# VariablePWMDriverSchematic.net
KiCad netlist of a schematic drawn in Altium Designer
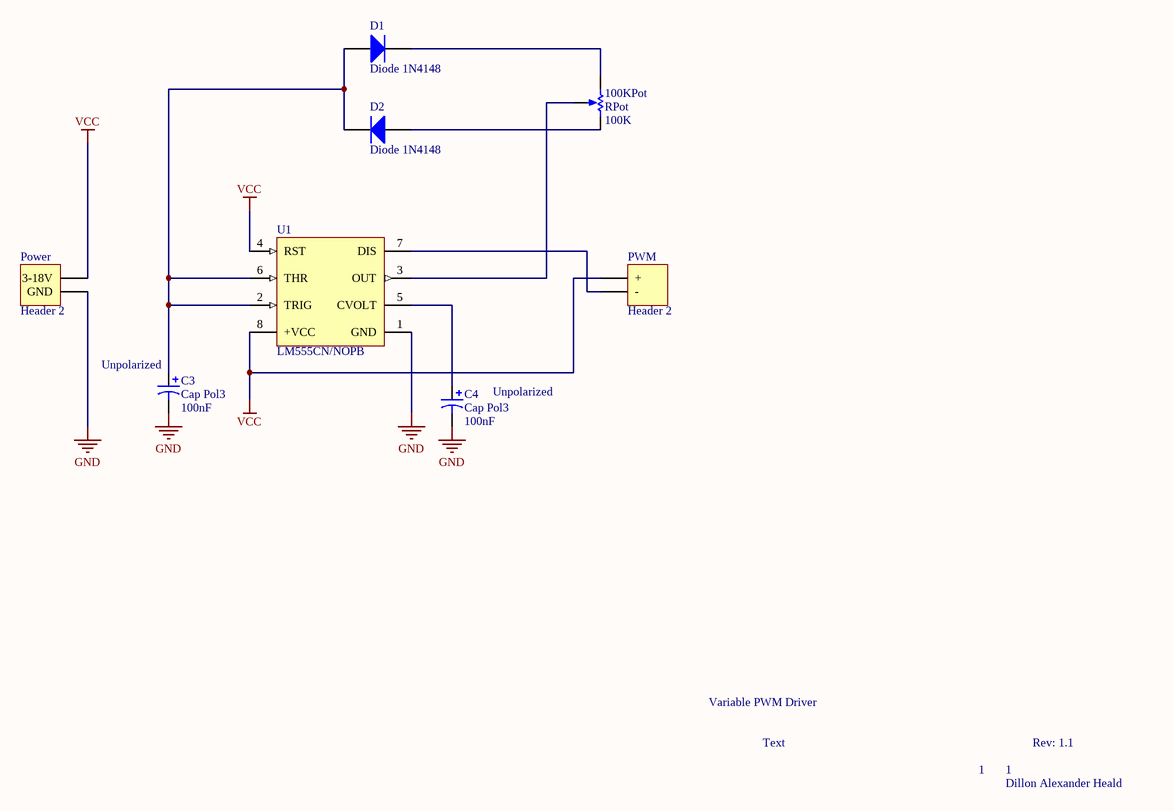
[diagram p0: VariablePWMDriverSchematic.SchDoc]

(export (version "E")
  (design (tool "Eeschema 10.0.6"))
  (components
    (comp (ref "100KPot")
      (value "RPot")
      (footprint "VR5")
      (description "Potentiometer")
      (fields (field (name "ALTIUM_VALUE") "100K") (field (name "PUBLISHER") "Altium Limited"))
      (libsource (lib "Miscellaneous Devices") (part "RPot"))
    )
    (comp (ref "C3")
      (value "Cap Pol3")
      (footprint "C0805")
      (description "Polarized Capacitor (Surface Mount)")
      (fields (field (name "ALTIUM_VALUE") "100nF") (field (name "PUBLISHER") "Altium Limited"))
      (libsource (lib "Miscellaneous Devices") (part "Cap Pol3"))
    )
    (comp (ref "C4")
      (value "Cap Pol3")
      (footprint "C0805")
      (description "Polarized Capacitor (Surface Mount)")
      (fields (field (name "ALTIUM_VALUE") "100nF") (field (name "PUBLISHER") "Altium Limited"))
      (libsource (lib "Miscellaneous Devices") (part "Cap Pol3"))
    )
    (comp (ref "D1")
      (value "Diode 1N4148")
      (footprint "DO-35")
      (description "High Conductance Fast Diode")
      (fields (field (name "PUBLISHER") "Altium Limited"))
      (libsource (lib "Miscellaneous Devices") (part "Diode 1N4148"))
    )
    (comp (ref "D2")
      (value "Diode 1N4148")
      (footprint "DO-35")
      (description "High Conductance Fast Diode")
      (fields (field (name "PUBLISHER") "Altium Limited"))
      (libsource (lib "Miscellaneous Devices") (part "Diode 1N4148"))
    )
    (comp (ref "Power")
      (value "Header 2")
      (footprint "HDR1X2")
      (description "Header, 2-Pin")
      (fields (field (name "PUBLISHER") "Altium Limited"))
      (libsource (lib "") (part "Header 2_1"))
    )
    (comp (ref "PWM")
      (value "Header 2")
      (footprint "HDR1X2")
      (description "Header, 2-Pin")
      (fields (field (name "PUBLISHER") "Altium Limited"))
      (libsource (lib "Miscellaneous Connectors") (part "Header 2"))
    )
    (comp (ref "U1")
      (value "LM555CN/NOPB")
      (footprint "N08E")
      (description "Timer, 8-pin MDIP, Pb-Free")
      (fields (field (name "MANUFACTURER") "National Semiconductor"))
      (libsource (lib "Altium Content Vault") (part "AN-TIMER-LM555-8"))
    )
  )
  (nets
    (net (code "1") (name "GND") (class "Default")
      (node (ref "C3") (pin "2") (pinfunction "2_2") (pintype "passive"))
      (node (ref "C4") (pin "2") (pinfunction "2_2") (pintype "passive"))
      (node (ref "Power") (pin "2") (pinfunction "GND_2") (pintype "passive"))
      (node (ref "U1") (pin "1") (pinfunction "GND_1") (pintype "power_in"))
    )
    (net (code "2") (name "Net-(100KPot-BOT)") (class "Default")
      (node (ref "100KPot") (pin "2") (pinfunction "BOT_2") (pintype "passive"))
      (node (ref "D2") (pin "1") (pinfunction "A_1") (pintype "passive"))
    )
    (net (code "3") (name "Net-(100KPot-TAP)") (class "Default")
      (node (ref "100KPot") (pin "3") (pinfunction "TAP_3") (pintype "passive"))
      (node (ref "U1") (pin "3") (pinfunction "OUT_3") (pintype "output"))
    )
    (net (code "4") (name "Net-(100KPot-TOP)") (class "Default")
      (node (ref "100KPot") (pin "1") (pinfunction "TOP_1") (pintype "passive"))
      (node (ref "D1") (pin "2") (pinfunction "K_2") (pintype "passive"))
    )
    (net (code "5") (name "Net-(D1-A)") (class "Default")
      (node (ref "C3") (pin "1") (pinfunction "1_1") (pintype "passive"))
      (node (ref "D1") (pin "1") (pinfunction "A_1") (pintype "passive"))
      (node (ref "D2") (pin "2") (pinfunction "K_2") (pintype "passive"))
      (node (ref "U1") (pin "2") (pinfunction "TRIG_2") (pintype "input"))
      (node (ref "U1") (pin "6") (pinfunction "THR_6") (pintype "input"))
    )
    (net (code "6") (name "Net-(PWM--)") (class "Default")
      (node (ref "PWM") (pin "2") (pinfunction "-_2") (pintype "passive"))
      (node (ref "U1") (pin "7") (pinfunction "DIS_7") (pintype "open_collector"))
    )
    (net (code "7") (name "Net-(U1-CVOLT)") (class "Default")
      (node (ref "C4") (pin "1") (pinfunction "1_1") (pintype "passive"))
      (node (ref "U1") (pin "5") (pinfunction "CVOLT_5") (pintype "passive"))
    )
    (net (code "8") (name "VCC") (class "Default")
      (node (ref "PWM") (pin "1") (pinfunction "+_1") (pintype "passive"))
      (node (ref "Power") (pin "1") (pinfunction "3-18V_1") (pintype "passive"))
      (node (ref "U1") (pin "4") (pinfunction "RST_4") (pintype "input"))
      (node (ref "U1") (pin "8") (pinfunction "+VCC_8") (pintype "power_in"))
    )
  )
)
